# RedBoard-v21.net
KiCad netlist of a schematic drawn in EAGLE
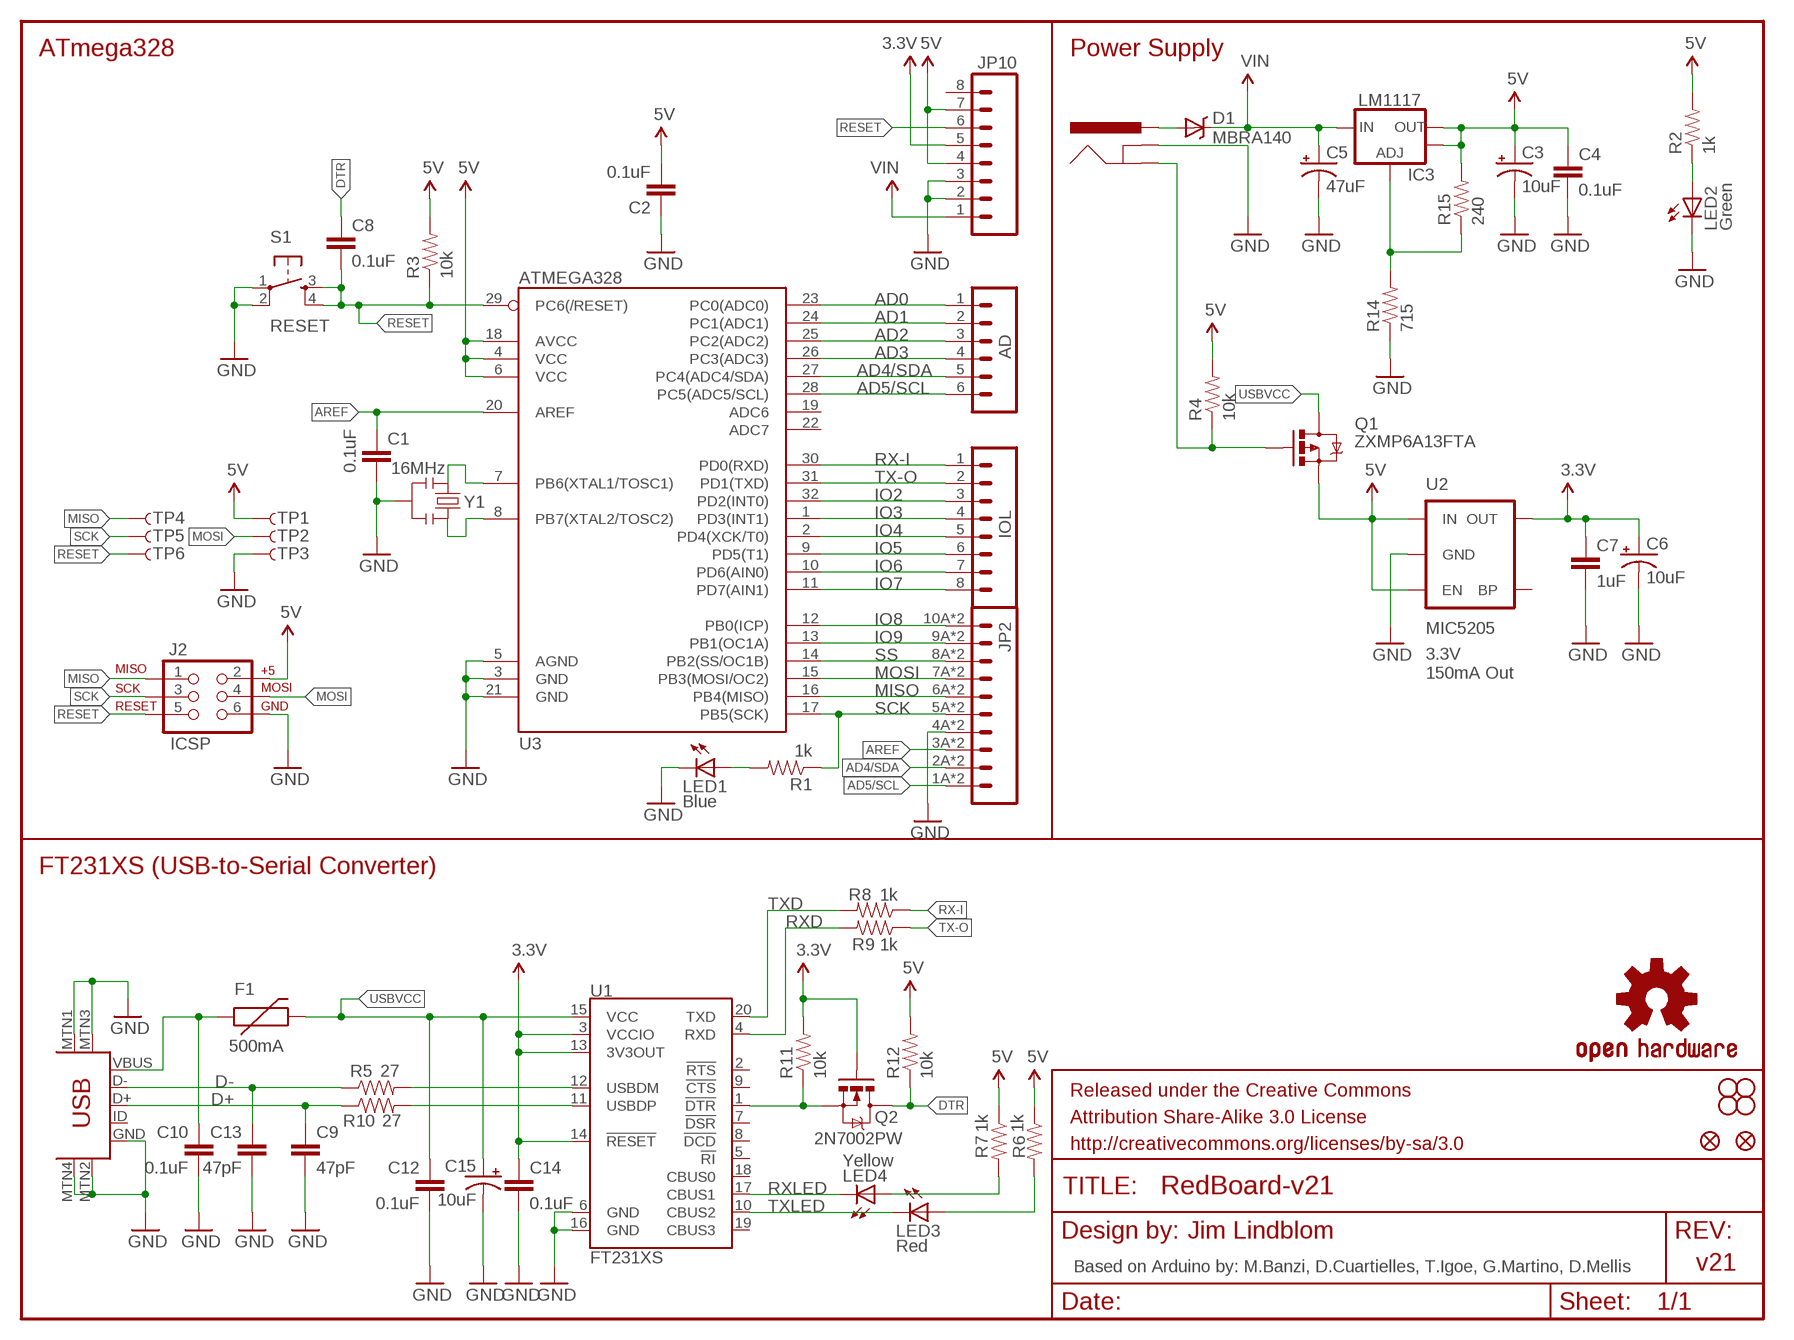
[diagram p0: schematic, sheet 1]

(export (version "E")
  (design (tool "Eeschema 10.0.6"))
  (components
    (comp (ref "AD")
      (value "M06SMD-STRAIGHT-COMBO")
      (footprint "eagle-import:1X06_SMD_STRAIGHT_COMBO")
      (libsource (lib "eagle-import") (part "M06SMD-STRAIGHT-COMBO"))
    )
    (comp (ref "C1")
      (value "0.1uF")
      (footprint "eagle-import:0603-CAP")
      (libsource (lib "eagle-import") (part "CAP0603-CAP"))
    )
    (comp (ref "C2")
      (value "0.1uF")
      (footprint "eagle-import:0603-CAP")
      (libsource (lib "eagle-import") (part "CAP0603-CAP"))
    )
    (comp (ref "C3")
      (value "10uF")
      (footprint "eagle-import:EIA3216")
      (libsource (lib "eagle-import") (part "CAP_POL1206"))
    )
    (comp (ref "C4")
      (value "0.1uF")
      (footprint "eagle-import:0603-CAP")
      (libsource (lib "eagle-import") (part "CAP0603-CAP"))
    )
    (comp (ref "C5")
      (value "47uF")
      (footprint "eagle-import:PANASONIC_D")
      (libsource (lib "eagle-import") (part "CAP_POLD"))
    )
    (comp (ref "C6")
      (value "10uF")
      (footprint "eagle-import:EIA3216")
      (libsource (lib "eagle-import") (part "CAP_POL1206"))
    )
    (comp (ref "C7")
      (value "1uF")
      (footprint "eagle-import:0603-CAP")
      (libsource (lib "eagle-import") (part "CAP0603-CAP"))
    )
    (comp (ref "C8")
      (value "0.1uF")
      (footprint "eagle-import:0603-CAP")
      (libsource (lib "eagle-import") (part "CAP0603-CAP"))
    )
    (comp (ref "C9")
      (value "47pF")
      (footprint "eagle-import:0603-CAP")
      (libsource (lib "eagle-import") (part "47PF-50V-5%(0603)"))
    )
    (comp (ref "C10")
      (value "0.1uF")
      (footprint "eagle-import:0603-CAP")
      (libsource (lib "eagle-import") (part "CAP0603-CAP"))
    )
    (comp (ref "C12")
      (value "0.1uF")
      (footprint "eagle-import:0603-CAP")
      (libsource (lib "eagle-import") (part "CAP0603-CAP"))
    )
    (comp (ref "C13")
      (value "47pF")
      (footprint "eagle-import:0603-CAP")
      (libsource (lib "eagle-import") (part "47PF-50V-5%(0603)"))
    )
    (comp (ref "C14")
      (value "0.1uF")
      (footprint "eagle-import:0603-CAP")
      (libsource (lib "eagle-import") (part "CAP0603-CAP"))
    )
    (comp (ref "C15")
      (value "10uF")
      (footprint "eagle-import:EIA3216")
      (libsource (lib "eagle-import") (part "SparkFun-Capacitors_CAP_POL1206"))
    )
    (comp (ref "D1")
      (value "MBRA140")
      (footprint "eagle-import:SMA-DIODE")
      (libsource (lib "eagle-import") (part "DIODE-SCHOTTKY_"))
    )
    (comp (ref "F1")
      (value "500mA")
      (footprint "eagle-import:PTC-1206")
      (libsource (lib "eagle-import") (part "PTCSMD"))
    )
    (comp (ref "FRAME2")
      (value "FRAME-LETTER")
      (footprint "eagle-import:CREATIVE_COMMONS")
      (libsource (lib "eagle-import") (part "FRAME-LETTER"))
    )
    (comp (ref "IC3")
      (value "LM1117")
      (footprint "eagle-import:SOT223-ALT1")
      (libsource (lib "eagle-import") (part "V_REG_LM1117ALT1"))
    )
    (comp (ref "IOL")
      (value "M08SMD-COMBO")
      (footprint "eagle-import:1X08_SMD_COMBINED")
      (libsource (lib "eagle-import") (part "M08SMD-COMBO"))
    )
    (comp (ref "J1")
      (value "POWER_JACKOVERPASTE_REDBOARD_0603")
      (footprint "eagle-import:POWER_JACK_SMD_OVERPASTE_REDBOARD_0603")
      (libsource (lib "eagle-import") (part "POWER_JACKOVERPASTE_REDBOARD_0603"))
    )
    (comp (ref "J2")
      (value "ICSP")
      (footprint "eagle-import:2X3_SMT_POSTS")
      (libsource (lib "eagle-import") (part "AVR_SPI_PRG_6SMT_MALE"))
    )
    (comp (ref "JP2")
      (value "M10SMD_COMBO")
      (footprint "eagle-import:1X10_SMD_COMBINED")
      (libsource (lib "eagle-import") (part "M10SMD_COMBO"))
    )
    (comp (ref "JP3")
      (value "STAND-OFF")
      (footprint "eagle-import:STAND-OFF")
      (libsource (lib "eagle-import") (part "STAND-OFF"))
    )
    (comp (ref "JP4")
      (value "STAND-OFF")
      (footprint "eagle-import:STAND-OFF")
      (libsource (lib "eagle-import") (part "STAND-OFF"))
    )
    (comp (ref "JP5")
      (value "STAND-OFF")
      (footprint "eagle-import:STAND-OFF")
      (libsource (lib "eagle-import") (part "STAND-OFF"))
    )
    (comp (ref "JP6")
      (value "STAND-OFF")
      (footprint "eagle-import:STAND-OFF")
      (libsource (lib "eagle-import") (part "STAND-OFF"))
    )
    (comp (ref "JP8")
      (value "FIDUCIAL1X2")
      (footprint "eagle-import:FIDUCIAL-1X2")
      (libsource (lib "eagle-import") (part "FIDUCIAL1X2"))
    )
    (comp (ref "JP9")
      (value "FIDUCIAL1X2")
      (footprint "eagle-import:FIDUCIAL-1X2")
      (libsource (lib "eagle-import") (part "FIDUCIAL1X2"))
    )
    (comp (ref "JP10")
      (value "M08SMD-COMBO")
      (footprint "eagle-import:1X08_SMD_COMBINED")
      (libsource (lib "eagle-import") (part "SparkFun-Connectors_M08SMD-COMBO"))
    )
    (comp (ref "LED1")
      (value "Blue")
      (footprint "eagle-import:LED-1206-NO_SILK")
      (libsource (lib "eagle-import") (part "LED1206-NS"))
    )
    (comp (ref "LED2")
      (value "Green")
      (footprint "eagle-import:LED-1206-NO_SILK")
      (libsource (lib "eagle-import") (part "LED1206-NS"))
    )
    (comp (ref "LED3")
      (value "Red")
      (footprint "eagle-import:LED-1206-NO_SILK")
      (libsource (lib "eagle-import") (part "LED1206-NS"))
    )
    (comp (ref "LED4")
      (value "Yellow")
      (footprint "eagle-import:LED-1206-NO_SILK")
      (libsource (lib "eagle-import") (part "LED1206-NS"))
    )
    (comp (ref "Q1")
      (value "ZXMP6A13FTA")
      (footprint "eagle-import:SOT23-3")
      (libsource (lib "eagle-import") (part "MOSFET-PCHANNELSMD"))
    )
    (comp (ref "Q2")
      (value "2N7002PW")
      (footprint "eagle-import:SOT323")
      (libsource (lib "eagle-import") (part "MOSFET-NCHANNEL2N7002PW"))
    )
    (comp (ref "R1")
      (value "1k")
      (footprint "eagle-import:0603-RES")
      (libsource (lib "eagle-import") (part "RESISTOR0603-RES"))
    )
    (comp (ref "R2")
      (value "1k")
      (footprint "eagle-import:0603-RES")
      (libsource (lib "eagle-import") (part "RESISTOR0603-RES"))
    )
    (comp (ref "R3")
      (value "10k")
      (footprint "eagle-import:0603-RES")
      (libsource (lib "eagle-import") (part "RESISTOR0603-RES"))
    )
    (comp (ref "R4")
      (value "10k")
      (footprint "eagle-import:0603-RES")
      (libsource (lib "eagle-import") (part "RESISTOR0603-RES"))
    )
    (comp (ref "R5")
      (value "27")
      (footprint "eagle-import:0603-RES")
      (libsource (lib "eagle-import") (part "SparkFun-Resistors_RESISTOR0603-RES"))
    )
    (comp (ref "R6")
      (value "1k")
      (footprint "eagle-import:0603-RES")
      (libsource (lib "eagle-import") (part "RESISTOR0603-RES"))
    )
    (comp (ref "R7")
      (value "1k")
      (footprint "eagle-import:0603-RES")
      (libsource (lib "eagle-import") (part "RESISTOR0603-RES"))
    )
    (comp (ref "R8")
      (value "1k")
      (footprint "eagle-import:0603-RES")
      (libsource (lib "eagle-import") (part "RESISTOR0603-RES"))
    )
    (comp (ref "R9")
      (value "1k")
      (footprint "eagle-import:0603-RES")
      (libsource (lib "eagle-import") (part "RESISTOR0603-RES"))
    )
    (comp (ref "R10")
      (value "27")
      (footprint "eagle-import:0603-RES")
      (libsource (lib "eagle-import") (part "SparkFun-Resistors_RESISTOR0603-RES"))
    )
    (comp (ref "R11")
      (value "10k")
      (footprint "eagle-import:0603-RES")
      (libsource (lib "eagle-import") (part "RESISTOR0603-RES"))
    )
    (comp (ref "R12")
      (value "10k")
      (footprint "eagle-import:0603-RES")
      (libsource (lib "eagle-import") (part "RESISTOR0603-RES"))
    )
    (comp (ref "R14")
      (value "715")
      (footprint "eagle-import:0603-RES")
      (libsource (lib "eagle-import") (part "RESISTOR0603-RES"))
    )
    (comp (ref "R15")
      (value "240")
      (footprint "eagle-import:0603-RES")
      (libsource (lib "eagle-import") (part "RESISTOR0603-RES"))
    )
    (comp (ref "S1")
      (value "RESET")
      (footprint "eagle-import:TACTILE_SWITCH_SMD")
      (libsource (lib "eagle-import") (part "TAC_SWITCHSMD"))
    )
    (comp (ref "TP1")
      (value "TP-3x5")
      (footprint "eagle-import:PAD.03X.05")
      (libsource (lib "eagle-import") (part "TEST-POINT3X5"))
    )
    (comp (ref "TP2")
      (value "TP-3x5")
      (footprint "eagle-import:PAD.03X.05")
      (libsource (lib "eagle-import") (part "TEST-POINT3X5"))
    )
    (comp (ref "TP3")
      (value "TP-3x5")
      (footprint "eagle-import:PAD.03X.05")
      (libsource (lib "eagle-import") (part "TEST-POINT3X5"))
    )
    (comp (ref "TP4")
      (value "TP-3x5")
      (footprint "eagle-import:PAD.03X.05")
      (libsource (lib "eagle-import") (part "TEST-POINT3X5"))
    )
    (comp (ref "TP5")
      (value "TP-3x5")
      (footprint "eagle-import:PAD.03X.05")
      (libsource (lib "eagle-import") (part "TEST-POINT3X5"))
    )
    (comp (ref "TP6")
      (value "TP-3x5")
      (footprint "eagle-import:PAD.03X.05")
      (libsource (lib "eagle-import") (part "TEST-POINT3X5"))
    )
    (comp (ref "U$13")
      (value "USB-MINIB-5PIN")
      (footprint "eagle-import:USB-MINIB")
      (libsource (lib "eagle-import") (part "USB-MINIB-5PIN"))
    )
    (comp (ref "U$16")
      (value "OSHW-LOGOS")
      (footprint "eagle-import:OSHW-LOGO-S")
      (libsource (lib "eagle-import") (part "OSHW-LOGOS"))
    )
    (comp (ref "U1")
      (value "FT231XS")
      (footprint "eagle-import:SSOP20_L")
      (libsource (lib "eagle-import") (part "FT231XS"))
    )
    (comp (ref "U2")
      (value "MIC5205")
      (footprint "eagle-import:SOT23-5")
      (libsource (lib "eagle-import") (part "V_REG_LDOSMD"))
    )
    (comp (ref "U3")
      (value "ATMEGA328")
      (footprint "eagle-import:TQFP32-08")
      (libsource (lib "eagle-import") (part "ATMEGA168"))
    )
    (comp (ref "Y1")
      (value "16MHz")
      (footprint "eagle-import:RESONATOR-SMD")
      (libsource (lib "eagle-import") (part "RESONATORSMD"))
    )
  )
  (nets
    (net (code "1") (name "/AD0") (class "Default")
      (node (ref "AD") (pin "1") (pinfunction "1_1") (pintype "passive"))
      (node (ref "U3") (pin "23") (pinfunction "PC0(ADC0)_23") (pintype "bidirectional"))
    )
    (net (code "2") (name "/AD1") (class "Default")
      (node (ref "AD") (pin "2") (pinfunction "2_2") (pintype "passive"))
      (node (ref "U3") (pin "24") (pinfunction "PC1(ADC1)_24") (pintype "bidirectional"))
    )
    (net (code "3") (name "/AD2") (class "Default")
      (node (ref "AD") (pin "3") (pinfunction "3_3") (pintype "passive"))
      (node (ref "U3") (pin "25") (pinfunction "PC2(ADC2)_25") (pintype "bidirectional"))
    )
    (net (code "4") (name "/AD3") (class "Default")
      (node (ref "AD") (pin "4") (pinfunction "4_4") (pintype "passive"))
      (node (ref "U3") (pin "26") (pinfunction "PC3(ADC3)_26") (pintype "bidirectional"))
    )
    (net (code "5") (name "/D+") (class "Default")
      (node (ref "C9") (pin "1") (pinfunction "1_1") (pintype "passive"))
      (node (ref "R10") (pin "1") (pinfunction "1_1") (pintype "passive"))
      (node (ref "U$13") (pin "D+") (pinfunction "D+_D+") (pintype "bidirectional"))
    )
    (net (code "6") (name "/D-") (class "Default")
      (node (ref "C13") (pin "1") (pinfunction "1_1") (pintype "passive"))
      (node (ref "R5") (pin "1") (pinfunction "1_1") (pintype "passive"))
      (node (ref "U$13") (pin "D-") (pinfunction "D-_D-") (pintype "bidirectional"))
    )
    (net (code "7") (name "/IO2") (class "Default")
      (node (ref "IOL") (pin "3") (pinfunction "3_3") (pintype "passive"))
      (node (ref "U3") (pin "32") (pinfunction "PD2(INT0)_32") (pintype "bidirectional"))
    )
    (net (code "8") (name "/IO3") (class "Default")
      (node (ref "IOL") (pin "4") (pinfunction "4_4") (pintype "passive"))
      (node (ref "U3") (pin "1") (pinfunction "PD3(INT1)_1") (pintype "bidirectional"))
    )
    (net (code "9") (name "/IO4") (class "Default")
      (node (ref "IOL") (pin "5") (pinfunction "5_5") (pintype "passive"))
      (node (ref "U3") (pin "2") (pinfunction "PD4(XCK/T0)_2") (pintype "bidirectional"))
    )
    (net (code "10") (name "/IO5") (class "Default")
      (node (ref "IOL") (pin "6") (pinfunction "6_6") (pintype "passive"))
      (node (ref "U3") (pin "9") (pinfunction "PD5(T1)_9") (pintype "bidirectional"))
    )
    (net (code "11") (name "/IO6") (class "Default")
      (node (ref "IOL") (pin "7") (pinfunction "7_7") (pintype "passive"))
      (node (ref "U3") (pin "10") (pinfunction "PD6(AIN0)_10") (pintype "bidirectional"))
    )
    (net (code "12") (name "/IO7") (class "Default")
      (node (ref "IOL") (pin "8") (pinfunction "8_8") (pintype "passive"))
      (node (ref "U3") (pin "11") (pinfunction "PD7(AIN1)_11") (pintype "bidirectional"))
    )
    (net (code "13") (name "/IO8") (class "Default")
      (node (ref "JP2") (pin "10A") (pinfunction "10_10A") (pintype "passive"))
      (node (ref "JP2") (pin "10B") (pinfunction "10_10B") (pintype "passive"))
      (node (ref "U3") (pin "12") (pinfunction "PB0(ICP)_12") (pintype "bidirectional"))
    )
    (net (code "14") (name "/IO9") (class "Default")
      (node (ref "JP2") (pin "9A") (pinfunction "9_9A") (pintype "passive"))
      (node (ref "JP2") (pin "9B") (pinfunction "9_9B") (pintype "passive"))
      (node (ref "U3") (pin "13") (pinfunction "PB1(OC1A)_13") (pintype "bidirectional"))
    )
    (net (code "15") (name "/RXD") (class "Default")
      (node (ref "R9") (pin "2") (pinfunction "2_2") (pintype "passive"))
      (node (ref "U1") (pin "4") (pinfunction "RXD_4") (pintype "bidirectional"))
    )
    (net (code "16") (name "/RXLED") (class "Default")
      (node (ref "LED4") (pin "C") (pinfunction "C_C") (pintype "passive"))
      (node (ref "U1") (pin "17") (pinfunction "CBUS1_17") (pintype "bidirectional"))
    )
    (net (code "17") (name "/SS") (class "Default")
      (node (ref "JP2") (pin "8A") (pinfunction "8_8A") (pintype "passive"))
      (node (ref "JP2") (pin "8B") (pinfunction "8_8B") (pintype "passive"))
      (node (ref "U3") (pin "14") (pinfunction "PB2(SS/OC1B)_14") (pintype "bidirectional"))
    )
    (net (code "18") (name "/TXD") (class "Default")
      (node (ref "R8") (pin "2") (pinfunction "2_2") (pintype "passive"))
      (node (ref "U1") (pin "20") (pinfunction "TXD_20") (pintype "bidirectional"))
    )
    (net (code "19") (name "/TXLED") (class "Default")
      (node (ref "LED3") (pin "C") (pinfunction "C_C") (pintype "passive"))
      (node (ref "U1") (pin "10") (pinfunction "CBUS2_10") (pintype "bidirectional"))
    )
    (net (code "20") (name "3.3V") (class "Default")
      (node (ref "C14") (pin "1") (pinfunction "1_1") (pintype "passive"))
      (node (ref "C6") (pin "A") (pinfunction "+_A") (pintype "passive"))
      (node (ref "C7") (pin "1") (pinfunction "1_1") (pintype "passive"))
      (node (ref "JP10") (pin "5") (pinfunction "5_5") (pintype "passive"))
      (node (ref "Q2") (pin "1") (pinfunction "G_1") (pintype "passive"))
      (node (ref "R11") (pin "2") (pinfunction "2_2") (pintype "passive"))
      (node (ref "U1") (pin "13") (pinfunction "3V3OUT_13") (pintype "bidirectional"))
      (node (ref "U1") (pin "14") (pinfunction "~{RESET}_14") (pintype "bidirectional"))
      (node (ref "U1") (pin "3") (pinfunction "VCCIO_3") (pintype "bidirectional"))
      (node (ref "U2") (pin "5") (pinfunction "OUT_5") (pintype "passive"))
    )
    (net (code "21") (name "5V") (class "Default")
      (node (ref "C2") (pin "2") (pinfunction "2_2") (pintype "passive"))
      (node (ref "C3") (pin "A") (pinfunction "+_A") (pintype "passive"))
      (node (ref "C4") (pin "1") (pinfunction "1_1") (pintype "passive"))
      (node (ref "IC3") (pin "2") (pinfunction "OUT_2") (pintype "output"))
      (node (ref "IC3") (pin "4") (pinfunction "OUT_4") (pintype "output"))
      (node (ref "J2") (pin "2") (pinfunction "2_2") (pintype "passive"))
      (node (ref "JP10") (pin "4") (pinfunction "4_4") (pintype "passive"))
      (node (ref "JP10") (pin "7") (pinfunction "7_7") (pintype "passive"))
      (node (ref "Q1") (pin "2") (pinfunction "S_2") (pintype "passive"))
      (node (ref "R12") (pin "2") (pinfunction "2_2") (pintype "passive"))
      (node (ref "R15") (pin "2") (pinfunction "2_2") (pintype "passive"))
      (node (ref "R2") (pin "2") (pinfunction "2_2") (pintype "passive"))
      (node (ref "R3") (pin "2") (pinfunction "2_2") (pintype "passive"))
      (node (ref "R4") (pin "2") (pinfunction "2_2") (pintype "passive"))
      (node (ref "R6") (pin "1") (pinfunction "1_1") (pintype "passive"))
      (node (ref "R7") (pin "1") (pinfunction "1_1") (pintype "passive"))
      (node (ref "TP1") (pin "P$1") (pinfunction "1_P$1") (pintype "bidirectional"))
      (node (ref "U2") (pin "1") (pinfunction "IN_1") (pintype "input"))
      (node (ref "U2") (pin "3") (pinfunction "EN_3") (pintype "input"))
      (node (ref "U3") (pin "18") (pinfunction "AVCC_18") (pintype "bidirectional"))
      (node (ref "U3") (pin "4") (pinfunction "VCC_4") (pintype "bidirectional"))
      (node (ref "U3") (pin "6") (pinfunction "VCC_6") (pintype "bidirectional"))
    )
    (net (code "22") (name "AD4{slash}SDA") (class "Default")
      (node (ref "AD") (pin "5") (pinfunction "5_5") (pintype "passive"))
      (node (ref "JP2") (pin "2A") (pinfunction "2_2A") (pintype "passive"))
      (node (ref "JP2") (pin "2B") (pinfunction "2_2B") (pintype "passive"))
      (node (ref "U3") (pin "27") (pinfunction "PC4(ADC4/SDA)_27") (pintype "bidirectional"))
    )
    (net (code "23") (name "AD5{slash}SCL") (class "Default")
      (node (ref "AD") (pin "6") (pinfunction "6_6") (pintype "passive"))
      (node (ref "JP2") (pin "1A") (pinfunction "1_1A") (pintype "passive"))
      (node (ref "JP2") (pin "1B") (pinfunction "1_1B") (pintype "passive"))
      (node (ref "U3") (pin "28") (pinfunction "PC5(ADC5/SCL)_28") (pintype "bidirectional"))
    )
    (net (code "24") (name "AREF") (class "Default")
      (node (ref "C1") (pin "1") (pinfunction "1_1") (pintype "passive"))
      (node (ref "JP2") (pin "3A") (pinfunction "3_3A") (pintype "passive"))
      (node (ref "JP2") (pin "3B") (pinfunction "3_3B") (pintype "passive"))
      (node (ref "U3") (pin "20") (pinfunction "AREF_20") (pintype "bidirectional"))
    )
    (net (code "25") (name "DTR") (class "Default")
      (node (ref "C8") (pin "1") (pinfunction "1_1") (pintype "passive"))
      (node (ref "Q2") (pin "3") (pinfunction "D_3") (pintype "passive"))
      (node (ref "R12") (pin "1") (pinfunction "1_1") (pintype "passive"))
    )
    (net (code "26") (name "GND") (class "Default")
      (node (ref "C1") (pin "2") (pinfunction "2_2") (pintype "passive"))
      (node (ref "C10") (pin "2") (pinfunction "2_2") (pintype "passive"))
      (node (ref "C12") (pin "2") (pinfunction "2_2") (pintype "passive"))
      (node (ref "C13") (pin "2") (pinfunction "2_2") (pintype "passive"))
      (node (ref "C14") (pin "2") (pinfunction "2_2") (pintype "passive"))
      (node (ref "C15") (pin "C") (pinfunction "-_C") (pintype "passive"))
      (node (ref "C2") (pin "1") (pinfunction "1_1") (pintype "passive"))
      (node (ref "C3") (pin "C") (pinfunction "-_C") (pintype "passive"))
      (node (ref "C4") (pin "2") (pinfunction "2_2") (pintype "passive"))
      (node (ref "C5") (pin "-") (pinfunction "-_-") (pintype "passive"))
      (node (ref "C6") (pin "C") (pinfunction "-_C") (pintype "passive"))
      (node (ref "C7") (pin "2") (pinfunction "2_2") (pintype "passive"))
      (node (ref "C9") (pin "2") (pinfunction "2_2") (pintype "passive"))
      (node (ref "J1") (pin "GND") (pinfunction "GNDBREAK_GND") (pintype "bidirectional"))
      (node (ref "J2") (pin "6") (pinfunction "6_6") (pintype "passive"))
      (node (ref "JP10") (pin "2") (pinfunction "2_2") (pintype "passive"))
      (node (ref "JP10") (pin "3") (pinfunction "3_3") (pintype "passive"))
      (node (ref "JP2") (pin "4A") (pinfunction "4_4A") (pintype "passive"))
      (node (ref "JP2") (pin "4B") (pinfunction "4_4B") (pintype "passive"))
      (node (ref "LED1") (pin "C") (pinfunction "C_C") (pintype "passive"))
      (node (ref "LED2") (pin "C") (pinfunction "C_C") (pintype "passive"))
      (node (ref "R14") (pin "1") (pinfunction "1_1") (pintype "passive"))
      (node (ref "S1") (pin "1") (pinfunction "1_1") (pintype "passive"))
      (node (ref "S1") (pin "2") (pinfunction "2_2") (pintype "passive"))
      (node (ref "TP3") (pin "P$1") (pinfunction "1_P$1") (pintype "bidirectional"))
      (node (ref "U$13") (pin "GND") (pinfunction "GND_GND") (pintype "bidirectional"))
      (node (ref "U$13") (pin "MTN1") (pinfunction "MTN2_MTN1") (pintype "bidirectional"))
      (node (ref "U$13") (pin "MTN2") (pinfunction "MTN3_MTN2") (pintype "bidirectional"))
      (node (ref "U$13") (pin "MTN3") (pinfunction "MTN1_MTN3") (pintype "bidirectional"))
      (node (ref "U$13") (pin "MTN4") (pinfunction "MTN4_MTN4") (pintype "bidirectional"))
      (node (ref "U1") (pin "16") (pinfunction "GND_16") (pintype "bidirectional"))
      (node (ref "U1") (pin "6") (pinfunction "GND_6") (pintype "bidirectional"))
      (node (ref "U2") (pin "2") (pinfunction "GND_2") (pintype "input"))
      (node (ref "U3") (pin "21") (pinfunction "GND_21") (pintype "bidirectional"))
      (node (ref "U3") (pin "3") (pinfunction "GND_3") (pintype "bidirectional"))
      (node (ref "U3") (pin "5") (pinfunction "AGND_5") (pintype "bidirectional"))
      (node (ref "Y1") (pin "2") (pinfunction "2_2") (pintype "passive"))
    )
    (net (code "27") (name "MISO") (class "Default")
      (node (ref "J2") (pin "1") (pinfunction "1_1") (pintype "passive"))
      (node (ref "JP2") (pin "6A") (pinfunction "6_6A") (pintype "passive"))
      (node (ref "JP2") (pin "6B") (pinfunction "6_6B") (pintype "passive"))
      (node (ref "TP4") (pin "P$1") (pinfunction "1_P$1") (pintype "bidirectional"))
      (node (ref "U3") (pin "16") (pinfunction "PB4(MISO)_16") (pintype "bidirectional"))
    )
    (net (code "28") (name "MOSI") (class "Default")
      (node (ref "J2") (pin "4") (pinfunction "4_4") (pintype "passive"))
      (node (ref "JP2") (pin "7A") (pinfunction "7_7A") (pintype "passive"))
      (node (ref "JP2") (pin "7B") (pinfunction "7_7B") (pintype "passive"))
      (node (ref "TP2") (pin "P$1") (pinfunction "1_P$1") (pintype "bidirectional"))
      (node (ref "U3") (pin "15") (pinfunction "PB3(MOSI/OC2)_15") (pintype "bidirectional"))
    )
    (net (code "29") (name "Net-(C10-Pad1)") (class "Default")
      (node (ref "C10") (pin "1") (pinfunction "1_1") (pintype "passive"))
      (node (ref "F1") (pin "1") (pinfunction "1_1") (pintype "bidirectional"))
      (node (ref "U$13") (pin "VBUS") (pinfunction "VBUS_VBUS") (pintype "bidirectional"))
    )
    (net (code "30") (name "Net-(IC3-ADJ)") (class "Default")
      (node (ref "IC3") (pin "1") (pinfunction "ADJ_1") (pintype "input"))
      (node (ref "R14") (pin "2") (pinfunction "2_2") (pintype "passive"))
      (node (ref "R15") (pin "1") (pinfunction "1_1") (pintype "passive"))
    )
    (net (code "31") (name "Net-(J1-GND)") (class "Default")
      (node (ref "J1") (pin "P$4") (pinfunction "GND_P$4") (pintype "bidirectional"))
      (node (ref "Q1") (pin "1") (pinfunction "G_1") (pintype "passive"))
      (node (ref "R4") (pin "1") (pinfunction "1_1") (pintype "passive"))
    )
    (net (code "32") (name "Net-(J1-PWR)") (class "Default")
      (node (ref "D1") (pin "A") (pinfunction "A_A") (pintype "passive"))
      (node (ref "J1") (pin "VIN0") (pinfunction "PWR_VIN0") (pintype "bidirectional"))
    )
    (net (code "33") (name "Net-(LED1-PadA)") (class "Default")
      (node (ref "LED1") (pin "A") (pinfunction "A_A") (pintype "passive"))
      (node (ref "R1") (pin "2") (pinfunction "2_2") (pintype "passive"))
    )
    (net (code "34") (name "Net-(LED2-PadA)") (class "Default")
      (node (ref "LED2") (pin "A") (pinfunction "A_A") (pintype "passive"))
      (node (ref "R2") (pin "1") (pinfunction "1_1") (pintype "passive"))
    )
    (net (code "35") (name "Net-(LED3-PadA)") (class "Default")
      (node (ref "LED3") (pin "A") (pinfunction "A_A") (pintype "passive"))
      (node (ref "R6") (pin "2") (pinfunction "2_2") (pintype "passive"))
    )
    (net (code "36") (name "Net-(LED4-PadA)") (class "Default")
      (node (ref "LED4") (pin "A") (pinfunction "A_A") (pintype "passive"))
      (node (ref "R7") (pin "2") (pinfunction "2_2") (pintype "passive"))
    )
    (net (code "37") (name "Net-(Q2-S)") (class "Default")
      (node (ref "Q2") (pin "2") (pinfunction "S_2") (pintype "passive"))
      (node (ref "R11") (pin "1") (pinfunction "1_1") (pintype "passive"))
      (node (ref "U1") (pin "1") (pinfunction "~{DTR}_1") (pintype "bidirectional"))
    )
    (net (code "38") (name "Net-(U1-USBDM)") (class "Default")
      (node (ref "R5") (pin "2") (pinfunction "2_2") (pintype "passive"))
      (node (ref "U1") (pin "12") (pinfunction "USBDM_12") (pintype "bidirectional"))
    )
    (net (code "39") (name "Net-(U1-USBDP)") (class "Default")
      (node (ref "R10") (pin "2") (pinfunction "2_2") (pintype "passive"))
      (node (ref "U1") (pin "11") (pinfunction "USBDP_11") (pintype "bidirectional"))
    )
    (net (code "40") (name "Net-(U3-PB6(XTAL1{slash}TOSC1))") (class "Default")
      (node (ref "U3") (pin "7") (pinfunction "PB6(XTAL1/TOSC1)_7") (pintype "bidirectional"))
      (node (ref "Y1") (pin "1") (pinfunction "1_1") (pintype "passive"))
    )
    (net (code "41") (name "Net-(U3-PB7(XTAL2{slash}TOSC2))") (class "Default")
      (node (ref "U3") (pin "8") (pinfunction "PB7(XTAL2/TOSC2)_8") (pintype "bidirectional"))
      (node (ref "Y1") (pin "3") (pinfunction "3_3") (pintype "passive"))
    )
    (net (code "42") (name "RESET") (class "Default")
      (node (ref "C8") (pin "2") (pinfunction "2_2") (pintype "passive"))
      (node (ref "J2") (pin "5") (pinfunction "5_5") (pintype "passive"))
      (node (ref "JP10") (pin "6") (pinfunction "6_6") (pintype "passive"))
      (node (ref "R3") (pin "1") (pinfunction "1_1") (pintype "passive"))
      (node (ref "S1") (pin "3") (pinfunction "3_3") (pintype "passive"))
      (node (ref "S1") (pin "4") (pinfunction "4_4") (pintype "passive"))
      (node (ref "TP6") (pin "P$1") (pinfunction "1_P$1") (pintype "bidirectional"))
      (node (ref "U3") (pin "29") (pinfunction "PC6(/RESET)_29") (pintype "bidirectional"))
    )
    (net (code "43") (name "RX-I") (class "Default")
      (node (ref "IOL") (pin "1") (pinfunction "1_1") (pintype "passive"))
      (node (ref "R8") (pin "1") (pinfunction "1_1") (pintype "passive"))
      (node (ref "U3") (pin "30") (pinfunction "PD0(RXD)_30") (pintype "bidirectional"))
    )
    (net (code "44") (name "SCK") (class "Default")
      (node (ref "J2") (pin "3") (pinfunction "3_3") (pintype "passive"))
      (node (ref "JP2") (pin "5A") (pinfunction "5_5A") (pintype "passive"))
      (node (ref "JP2") (pin "5B") (pinfunction "5_5B") (pintype "passive"))
      (node (ref "R1") (pin "1") (pinfunction "1_1") (pintype "passive"))
      (node (ref "TP5") (pin "P$1") (pinfunction "1_P$1") (pintype "bidirectional"))
      (node (ref "U3") (pin "17") (pinfunction "PB5(SCK)_17") (pintype "bidirectional"))
    )
    (net (code "45") (name "TX-O") (class "Default")
      (node (ref "IOL") (pin "2") (pinfunction "2_2") (pintype "passive"))
      (node (ref "R9") (pin "1") (pinfunction "1_1") (pintype "passive"))
      (node (ref "U3") (pin "31") (pinfunction "PD1(TXD)_31") (pintype "bidirectional"))
    )
    (net (code "46") (name "USBVCC") (class "Default")
      (node (ref "C12") (pin "1") (pinfunction "1_1") (pintype "passive"))
      (node (ref "C15") (pin "A") (pinfunction "+_A") (pintype "passive"))
      (node (ref "F1") (pin "2") (pinfunction "2_2") (pintype "bidirectional"))
      (node (ref "Q1") (pin "3") (pinfunction "D_3") (pintype "passive"))
      (node (ref "U1") (pin "15") (pinfunction "VCC_15") (pintype "bidirectional"))
    )
    (net (code "47") (name "VIN") (class "Default")
      (node (ref "C5") (pin "+") (pinfunction "+_+") (pintype "passive"))
      (node (ref "D1") (pin "C") (pinfunction "C_C") (pintype "passive"))
      (node (ref "IC3") (pin "3") (pinfunction "IN_3") (pintype "input"))
      (node (ref "JP10") (pin "1") (pinfunction "1_1") (pintype "passive"))
    )
    (net (code "48") (name "unconnected-(JP10-Pad8)") (class "Default")
      (node (ref "JP10") (pin "8") (pinfunction "8_8") (pintype "passive"))
    )
    (net (code "49") (name "unconnected-(U$13-PadID)") (class "Default")
      (node (ref "U$13") (pin "ID") (pinfunction "ID_ID") (pintype "bidirectional"))
    )
    (net (code "50") (name "unconnected-(U1-CBUS0-Pad18)") (class "Default")
      (node (ref "U1") (pin "18") (pinfunction "CBUS0_18") (pintype "bidirectional"))
    )
    (net (code "51") (name "unconnected-(U1-CBUS3-Pad19)") (class "Default")
      (node (ref "U1") (pin "19") (pinfunction "CBUS3_19") (pintype "bidirectional"))
    )
    (net (code "52") (name "unconnected-(U1-~{CTS}-Pad9)") (class "Default")
      (node (ref "U1") (pin "9") (pinfunction "~{CTS}_9") (pintype "bidirectional"))
    )
    (net (code "53") (name "unconnected-(U1-~{DCD}-Pad8)") (class "Default")
      (node (ref "U1") (pin "8") (pinfunction "~{DCD}_8") (pintype "bidirectional"))
    )
    (net (code "54") (name "unconnected-(U1-~{DSR}-Pad7)") (class "Default")
      (node (ref "U1") (pin "7") (pinfunction "~{DSR}_7") (pintype "bidirectional"))
    )
    (net (code "55") (name "unconnected-(U1-~{RI}-Pad5)") (class "Default")
      (node (ref "U1") (pin "5") (pinfunction "~{RI}_5") (pintype "bidirectional"))
    )
    (net (code "56") (name "unconnected-(U1-~{RTS}-Pad2)") (class "Default")
      (node (ref "U1") (pin "2") (pinfunction "~{RTS}_2") (pintype "bidirectional"))
    )
    (net (code "57") (name "unconnected-(U2-BP-Pad4)") (class "Default")
      (node (ref "U2") (pin "4") (pinfunction "BP_4") (pintype "input"))
    )
    (net (code "58") (name "unconnected-(U3-ADC6-Pad19)") (class "Default")
      (node (ref "U3") (pin "19") (pinfunction "ADC6_19") (pintype "bidirectional"))
    )
    (net (code "59") (name "unconnected-(U3-ADC7-Pad22)") (class "Default")
      (node (ref "U3") (pin "22") (pinfunction "ADC7_22") (pintype "bidirectional"))
    )
  )
)
